# InkTime.net
KiCad netlist of a schematic drawn in EAGLE
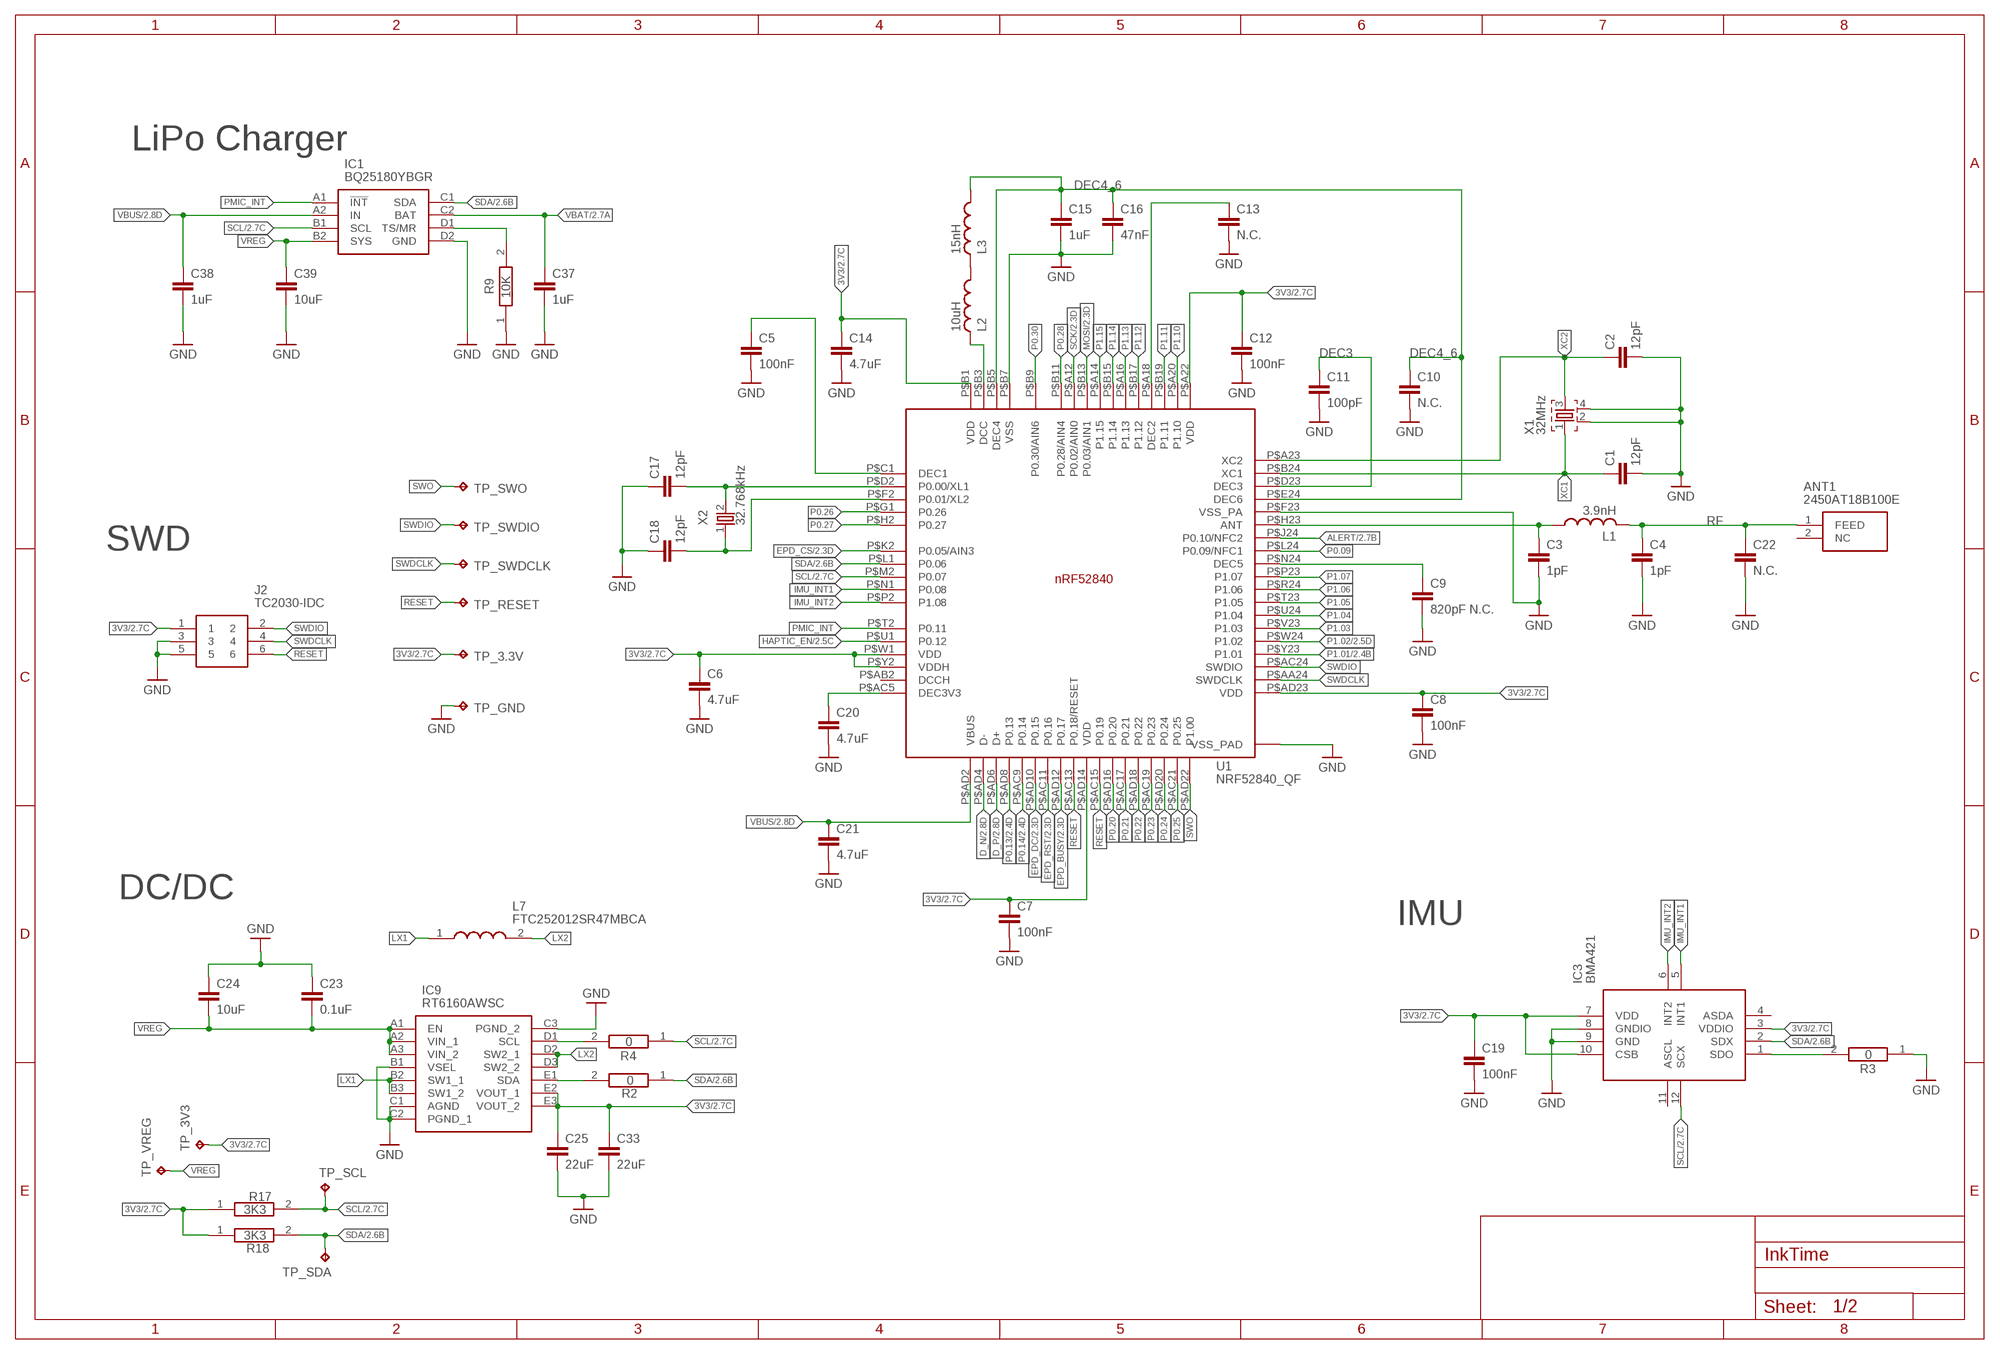
[diagram p0: schematic, sheet 1]
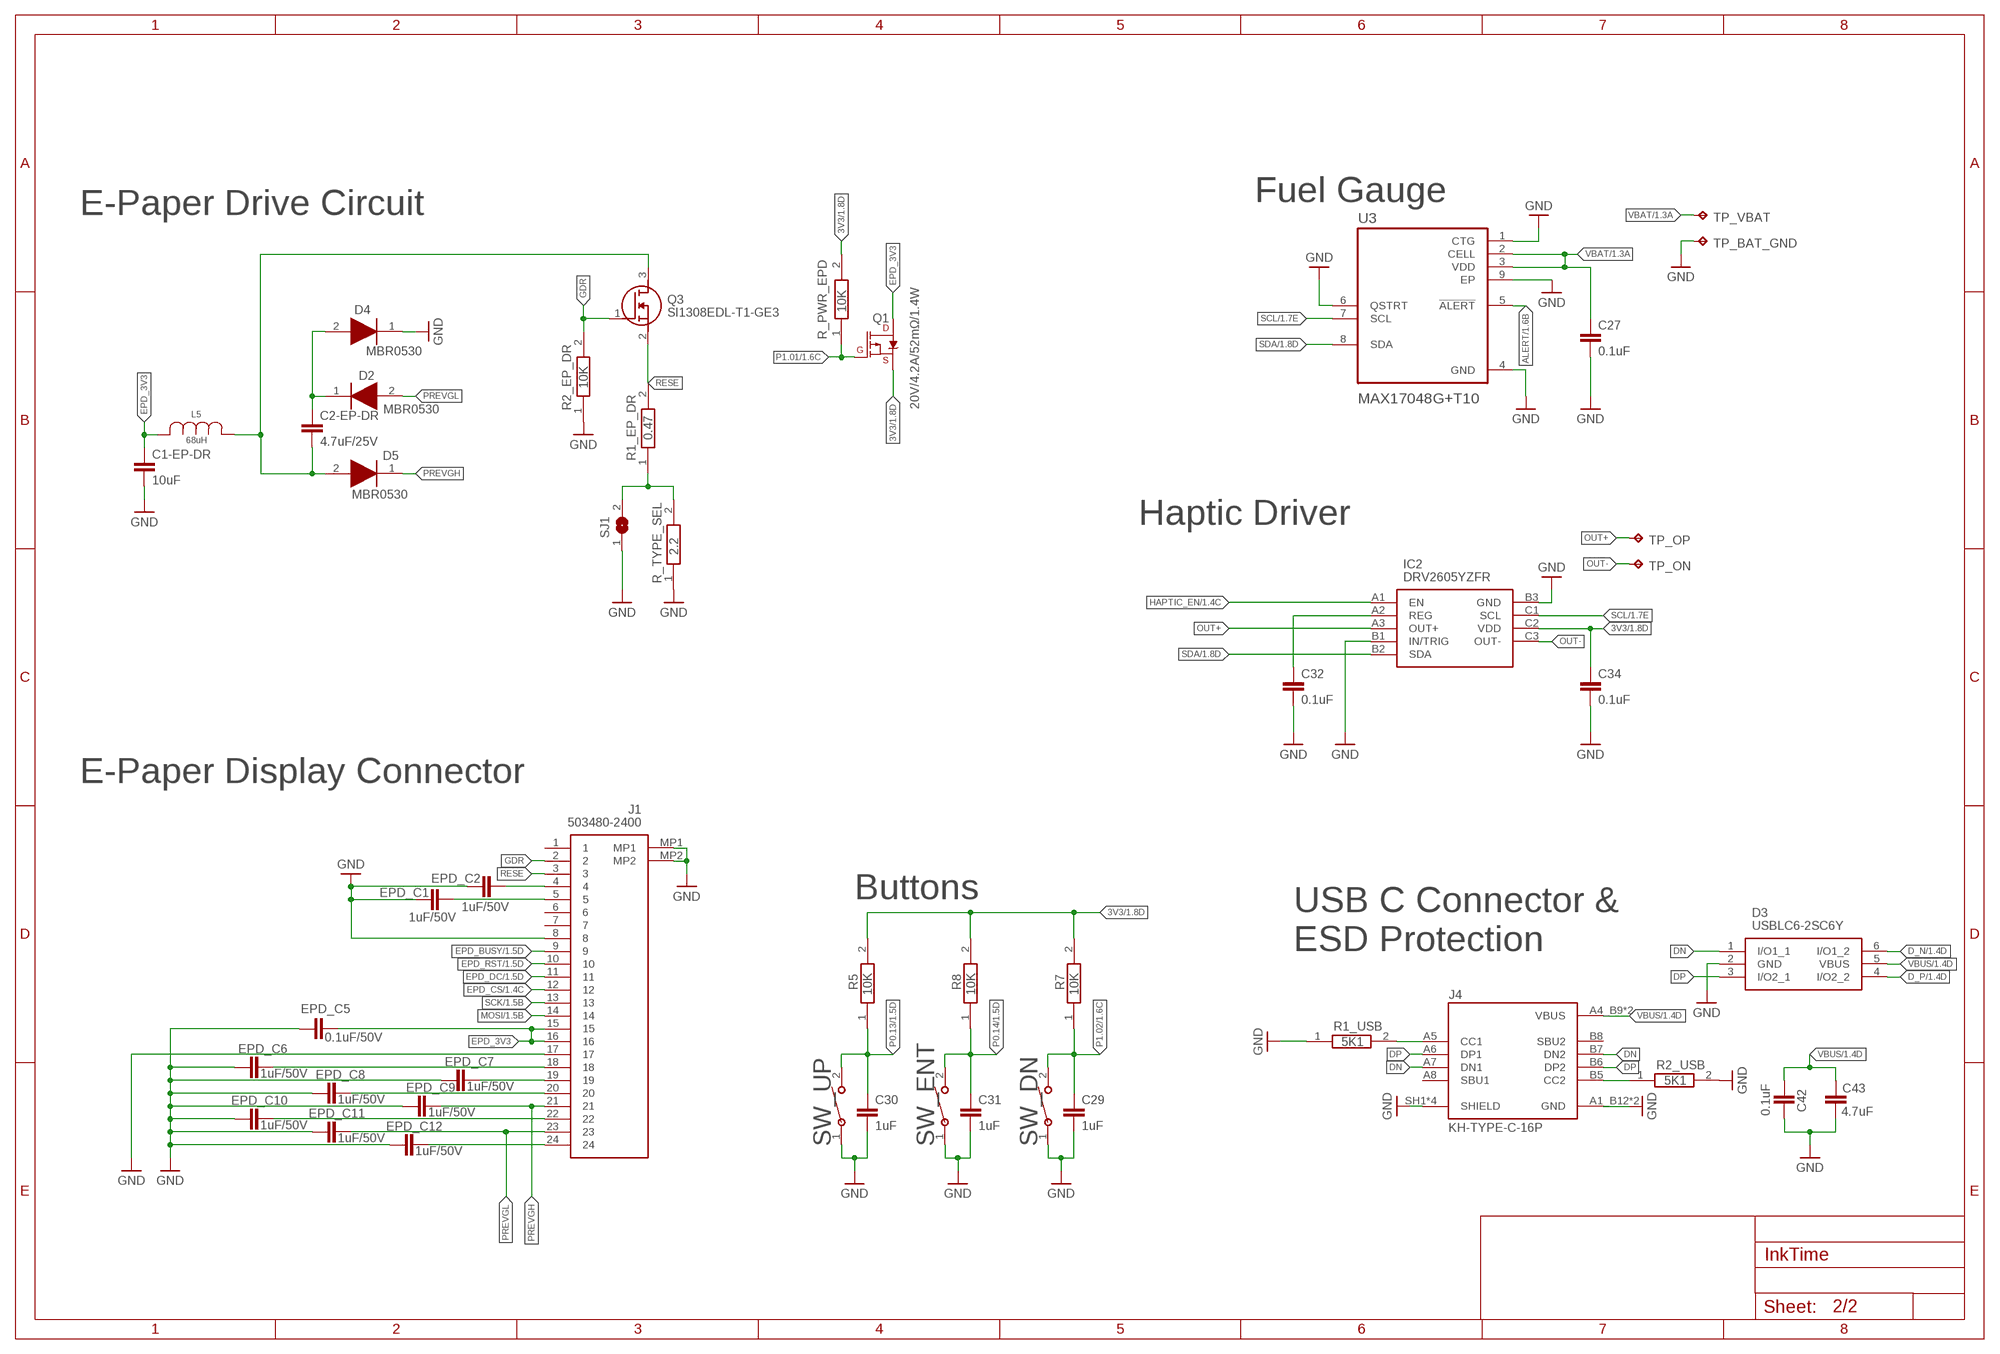
[diagram p1: schematic, sheet 2]

(export (version "E")
  (design (tool "Eeschema 10.0.6"))
  (components
    (comp (ref "C1-EP-DR")
      (value "10uF")
      (footprint "eagle-import:NORDIC_NRF_3_RESC0402_N")
      (libsource (lib "eagle-import") (part "NORDIC_NRF_3_CAPACITOR_0402_N"))
    )
    (comp (ref "C2-EP-DR")
      (value "4.7uF/25V")
      (footprint "eagle-import:NORDIC_NRF_3_RESC0402_N")
      (libsource (lib "eagle-import") (part "NORDIC_NRF_3_CAPACITOR_0402_N"))
    )
    (comp (ref "C27")
      (value "0.1uF")
      (footprint "eagle-import:NORDIC_NRF_3_RESC0201_N")
      (libsource (lib "eagle-import") (part "NORDIC_NRF_3_CAPACITOR_0201_N"))
    )
    (comp (ref "C29")
      (value "1uF")
      (footprint "eagle-import:NORDIC_NRF_3_RESC0402_N")
      (libsource (lib "eagle-import") (part "NORDIC_NRF_3_CAPACITOR_0402_N"))
    )
    (comp (ref "C30")
      (value "1uF")
      (footprint "eagle-import:NORDIC_NRF_3_RESC0402_N")
      (libsource (lib "eagle-import") (part "NORDIC_NRF_3_CAPACITOR_0402_N"))
    )
    (comp (ref "C31")
      (value "1uF")
      (footprint "eagle-import:NORDIC_NRF_3_RESC0402_N")
      (libsource (lib "eagle-import") (part "NORDIC_NRF_3_CAPACITOR_0402_N"))
    )
    (comp (ref "C32")
      (value "0.1uF")
      (footprint "eagle-import:NORDIC_NRF_3_RESC0201_N")
      (libsource (lib "eagle-import") (part "NORDIC_NRF_3_CAPACITOR_0201_N"))
    )
    (comp (ref "C34")
      (value "0.1uF")
      (footprint "eagle-import:NORDIC_NRF_3_RESC0201_N")
      (libsource (lib "eagle-import") (part "NORDIC_NRF_3_CAPACITOR_0201_N"))
    )
    (comp (ref "C42")
      (value "0.1uF")
      (footprint "eagle-import:NORDIC_NRF_3_RESC0201_N")
      (libsource (lib "eagle-import") (part "NORDIC_NRF_3_CAPACITOR_0201_N"))
    )
    (comp (ref "C43")
      (value "4.7uF")
      (footprint "eagle-import:NORDIC_NRF_3_RESC0402_N")
      (libsource (lib "eagle-import") (part "NORDIC_NRF_3_CAPACITOR_0402_N"))
    )
    (comp (ref "D2")
      (value "MBR0530")
      (footprint "eagle-import:ESP32_C6_LIBRARY_5_SOD3716X135N")
      (fields (field (name "MF") "ON Semiconductor"))
      (libsource (lib "eagle-import") (part "ESP32_C6_LIBRARY_5_MBR0530"))
    )
    (comp (ref "D3")
      (value "USBLC6-2SC6Y")
      (footprint "eagle-import:ESP32_C6_LIBRARY_3_SOT95P280X145-6N")
      (fields (field (name "MF") "STMicroelectronics"))
      (libsource (lib "eagle-import") (part "ESP32_C6_LIBRARY_3_USBLC6-2SC6Y"))
    )
    (comp (ref "D4")
      (value "MBR0530")
      (footprint "eagle-import:ESP32_C6_LIBRARY_5_SOD3716X135N")
      (fields (field (name "MF") "ON Semiconductor"))
      (libsource (lib "eagle-import") (part "ESP32_C6_LIBRARY_5_MBR0530"))
    )
    (comp (ref "D5")
      (value "MBR0530")
      (footprint "eagle-import:ESP32_C6_LIBRARY_5_SOD3716X135N")
      (fields (field (name "MF") "ON Semiconductor"))
      (libsource (lib "eagle-import") (part "ESP32_C6_LIBRARY_5_MBR0530"))
    )
    (comp (ref "EPD_C1")
      (value "1uF/50V")
      (footprint "eagle-import:NORDIC_NRF_3_RESC0402_N")
      (libsource (lib "eagle-import") (part "NORDIC_NRF_3_CAPACITOR_0402_N"))
    )
    (comp (ref "EPD_C2")
      (value "1uF/50V")
      (footprint "eagle-import:NORDIC_NRF_3_RESC0402_N")
      (libsource (lib "eagle-import") (part "NORDIC_NRF_3_CAPACITOR_0402_N"))
    )
    (comp (ref "EPD_C5")
      (value "0.1uF/50V")
      (footprint "eagle-import:NORDIC_NRF_3_RESC0402_N")
      (libsource (lib "eagle-import") (part "NORDIC_NRF_3_CAPACITOR_0402_N"))
    )
    (comp (ref "EPD_C6")
      (value "1uF/50V")
      (footprint "eagle-import:NORDIC_NRF_3_RESC0402_N")
      (libsource (lib "eagle-import") (part "NORDIC_NRF_3_CAPACITOR_0402_N"))
    )
    (comp (ref "EPD_C7")
      (value "1uF/50V")
      (footprint "eagle-import:NORDIC_NRF_3_RESC0402_N")
      (libsource (lib "eagle-import") (part "NORDIC_NRF_3_CAPACITOR_0402_N"))
    )
    (comp (ref "EPD_C8")
      (value "1uF/50V")
      (footprint "eagle-import:NORDIC_NRF_3_RESC0402_N")
      (libsource (lib "eagle-import") (part "NORDIC_NRF_3_CAPACITOR_0402_N"))
    )
    (comp (ref "EPD_C9")
      (value "1uF/50V")
      (footprint "eagle-import:NORDIC_NRF_3_RESC0402_N")
      (libsource (lib "eagle-import") (part "NORDIC_NRF_3_CAPACITOR_0402_N"))
    )
    (comp (ref "EPD_C10")
      (value "1uF/50V")
      (footprint "eagle-import:NORDIC_NRF_3_RESC0402_N")
      (libsource (lib "eagle-import") (part "NORDIC_NRF_3_CAPACITOR_0402_N"))
    )
    (comp (ref "EPD_C11")
      (value "1uF/50V")
      (footprint "eagle-import:NORDIC_NRF_3_RESC0402_N")
      (libsource (lib "eagle-import") (part "NORDIC_NRF_3_CAPACITOR_0402_N"))
    )
    (comp (ref "EPD_C12")
      (value "1uF/50V")
      (footprint "eagle-import:NORDIC_NRF_3_RESC0402_N")
      (libsource (lib "eagle-import") (part "NORDIC_NRF_3_CAPACITOR_0402_N"))
    )
    (comp (ref "IC2")
      (value "DRV2605YZFR")
      (footprint "eagle-import:DRV2605YZFR_BGA9C50P3X3_144X144X62")
      (libsource (lib "eagle-import") (part "DRV2605YZFR_DRV2605YZFR"))
    )
    (comp (ref "J1")
      (value "503480-2400")
      (footprint "eagle-import:503480-2400_5034802400")
      (fields (field (name "MOUSER_PART_NUMBER") "538-503480-2400"))
      (libsource (lib "eagle-import") (part "503480-2400_503480-24003D"))
    )
    (comp (ref "J4")
      (value "KH-TYPE-C-16P")
      (footprint "eagle-import:KH-TYPE-C-16P_KINGHELM_KH-TYPE-C-16P")
      (fields (field (name "MF") "kinghelm"))
      (libsource (lib "eagle-import") (part "KH-TYPE-C-16P_KH-TYPE-C-16P"))
    )
    (comp (ref "L5")
      (value "68uH")
      (footprint "eagle-import:ESP32_C6_LIBRARY_2_IND_4828-WE-TPC_WRE")
      (fields
        (field (name "MANUFACTURER_PART_NUMBER") "744043680")
        (field (name "COPYRIGHT") "Copyright (C) 2024 Ultra Librarian. All rights reserved.")
      )
      (libsource (lib "eagle-import") (part "ESP32_C6_LIBRARY_2_744043680IND_4828-WE-TPC_WRE"))
    )
    (comp (ref "Q1")
      (value "20V/4.2A/52mΩ/1.4W")
      (footprint "eagle-import:ESP32_C6_LIBRARY_4_ESP32_C6_LIBRARY_4_ESP32_C6_LIBRARY_4_ESP32_C6_LIBRARY_4_ESP32_WROVER_SPARKFUN-DISCRETESEMI_SOT23-3")
      (libsource (lib "eagle-import") (part "ESP32_C6_LIBRARY_4_ESP32_WROVER_SPARKFUN-DISCRETESEMI_MOSFET_PCH-DMG2305UX-7"))
    )
    (comp (ref "Q3")
      (value "SI1308EDL-T1-GE3")
      (footprint "eagle-import:ESP32_C6_LIBRARY_6_SOT65P210X110-3N")
      (fields (field (name "MF") "Vishay Siliconix"))
      (libsource (lib "eagle-import") (part "ESP32_C6_LIBRARY_6_SI1308EDL-T1-GE3"))
    )
    (comp (ref "R1_EP_DR")
      (value "0.47")
      (footprint "eagle-import:CPF0201D7K68C1_0201")
      (libsource (lib "eagle-import") (part "CPF0201D7K68C1_CPF0201D7K68C1"))
    )
    (comp (ref "R1_USB")
      (value "5K1")
      (footprint "eagle-import:CPF0201D7K68C1_0201")
      (libsource (lib "eagle-import") (part "CPF0201D7K68C1_CPF0201D7K68C1"))
    )
    (comp (ref "R2_EP_DR")
      (value "10K")
      (footprint "eagle-import:CPF0201D7K68C1_0201")
      (libsource (lib "eagle-import") (part "CPF0201D7K68C1_CPF0201D7K68C1"))
    )
    (comp (ref "R2_USB")
      (value "5K1")
      (footprint "eagle-import:CPF0201D7K68C1_0201")
      (libsource (lib "eagle-import") (part "CPF0201D7K68C1_CPF0201D7K68C1"))
    )
    (comp (ref "R5")
      (value "10K")
      (footprint "eagle-import:CPF0201D7K68C1_0201")
      (libsource (lib "eagle-import") (part "CPF0201D7K68C1_CPF0201D7K68C1"))
    )
    (comp (ref "R7")
      (value "10K")
      (footprint "eagle-import:CPF0201D7K68C1_0201")
      (libsource (lib "eagle-import") (part "CPF0201D7K68C1_CPF0201D7K68C1"))
    )
    (comp (ref "R8")
      (value "10K")
      (footprint "eagle-import:CPF0201D7K68C1_0201")
      (libsource (lib "eagle-import") (part "CPF0201D7K68C1_CPF0201D7K68C1"))
    )
    (comp (ref "R_PWR_EPD")
      (value "10K")
      (footprint "eagle-import:CPF0201D7K68C1_0201")
      (libsource (lib "eagle-import") (part "CPF0201D7K68C1_CPF0201D7K68C1"))
    )
    (comp (ref "R_TYPE_SEL")
      (value "2.2")
      (footprint "eagle-import:CPF0201D7K68C1_0201")
      (libsource (lib "eagle-import") (part "CPF0201D7K68C1_CPF0201D7K68C1"))
    )
    (comp (ref "SJ1")
      (value "ESP32_C6_LIBRARY_7_JUMPER_SJ")
      (footprint "eagle-import:ESP32_C6_LIBRARY_7_JUMPER_SJ")
      (libsource (lib "eagle-import") (part "ESP32_C6_LIBRARY_7_JUMPER_SJ"))
    )
    (comp (ref "SW_DN")
      (value "2025-10-22_07-23-44_LIBRARY_EVP-AKE31ASW_EVP-AKE31A_PAN")
      (footprint "eagle-import:2025-10-22_07-23-44_LIBRARY_SW_EVP-AKE31A_PAN")
      (fields
        (field (name "MANUFACTURER_PART_NUMBER") "EVP-AKE31A")
        (field (name "COPYRIGHT") "Copyright (C) 2025 Ultra Librarian. All rights reserved.")
      )
      (libsource (lib "eagle-import") (part "2025-10-22_07-23-44_LIBRARY_EVP-AKE31ASW_EVP-AKE31A_PAN"))
    )
    (comp (ref "SW_ENT")
      (value "2025-10-22_07-23-44_LIBRARY_EVP-AKE31ASW_EVP-AKE31A_PAN")
      (footprint "eagle-import:2025-10-22_07-23-44_LIBRARY_SW_EVP-AKE31A_PAN")
      (fields
        (field (name "MANUFACTURER_PART_NUMBER") "EVP-AKE31A")
        (field (name "COPYRIGHT") "Copyright (C) 2025 Ultra Librarian. All rights reserved.")
      )
      (libsource (lib "eagle-import") (part "2025-10-22_07-23-44_LIBRARY_EVP-AKE31ASW_EVP-AKE31A_PAN"))
    )
    (comp (ref "SW_UP")
      (value "2025-10-22_07-23-44_LIBRARY_EVP-AKE31ASW_EVP-AKE31A_PAN")
      (footprint "eagle-import:2025-10-22_07-23-44_LIBRARY_SW_EVP-AKE31A_PAN")
      (fields
        (field (name "MANUFACTURER_PART_NUMBER") "EVP-AKE31A")
        (field (name "COPYRIGHT") "Copyright (C) 2025 Ultra Librarian. All rights reserved.")
      )
      (libsource (lib "eagle-import") (part "2025-10-22_07-23-44_LIBRARY_EVP-AKE31ASW_EVP-AKE31A_PAN"))
    )
    (comp (ref "TP_BAT_GND")
      (value "HECTOR_WATCH_1_TPTP20R")
      (footprint "eagle-import:HECTOR_WATCH_1_TP20R")
      (libsource (lib "eagle-import") (part "HECTOR_WATCH_1_TPTP20R"))
    )
    (comp (ref "TP_ON")
      (value "HECTOR_WATCH_1_TPTP20R")
      (footprint "eagle-import:HECTOR_WATCH_1_TP20R")
      (libsource (lib "eagle-import") (part "HECTOR_WATCH_1_TPTP20R"))
    )
    (comp (ref "TP_OP")
      (value "HECTOR_WATCH_1_TPTP20R")
      (footprint "eagle-import:HECTOR_WATCH_1_TP20R")
      (libsource (lib "eagle-import") (part "HECTOR_WATCH_1_TPTP20R"))
    )
    (comp (ref "TP_VBAT")
      (value "HECTOR_WATCH_1_TPTP20R")
      (footprint "eagle-import:HECTOR_WATCH_1_TP20R")
      (libsource (lib "eagle-import") (part "HECTOR_WATCH_1_TPTP20R"))
    )
    (comp (ref "U3")
      (value "MAX17048G+T10")
      (footprint "eagle-import:ESP32_C6_LIBRARY_SON50P200X200X80-9N")
      (fields (field (name "MF") "Analog Devices"))
      (libsource (lib "eagle-import") (part "ESP32_C6_LIBRARY_MAX17048G+T10"))
    )
    (comp (ref "ANT1")
      (value "2450AT18B100E")
      (footprint "eagle-import:2450AT18B100E_ANTC3216X140N")
      (fields (field (name "MOUSER_PART_NUMBER") "609-2450AT18B100E"))
      (libsource (lib "eagle-import") (part "2450AT18B100E_2450AT18B100E3D"))
    )
    (comp (ref "C1")
      (value "12pF")
      (footprint "eagle-import:NORDIC_NRF_3_RESC0201_N")
      (libsource (lib "eagle-import") (part "NORDIC_NRF_3_CAPACITOR_0201_N"))
    )
    (comp (ref "C2")
      (value "12pF")
      (footprint "eagle-import:NORDIC_NRF_3_RESC0201_N")
      (libsource (lib "eagle-import") (part "NORDIC_NRF_3_CAPACITOR_0201_N"))
    )
    (comp (ref "C3")
      (value "1pF")
      (footprint "eagle-import:NORDIC_NRF_3_RESC0201_N")
      (libsource (lib "eagle-import") (part "NORDIC_NRF_3_CAPACITOR_0201_N"))
    )
    (comp (ref "C4")
      (value "1pF")
      (footprint "eagle-import:NORDIC_NRF_3_RESC0201_N")
      (libsource (lib "eagle-import") (part "NORDIC_NRF_3_CAPACITOR_0201_N"))
    )
    (comp (ref "C5")
      (value "100nF")
      (footprint "eagle-import:NORDIC_NRF_3_RESC0201_N")
      (libsource (lib "eagle-import") (part "NORDIC_NRF_3_CAPACITOR_0201_N"))
    )
    (comp (ref "C6")
      (value "4.7uF")
      (footprint "eagle-import:NORDIC_NRF_3_RESC0402_N")
      (libsource (lib "eagle-import") (part "NORDIC_NRF_3_CAPACITOR_0402_N"))
    )
    (comp (ref "C7")
      (value "100nF")
      (footprint "eagle-import:NORDIC_NRF_3_RESC0201_N")
      (libsource (lib "eagle-import") (part "NORDIC_NRF_3_CAPACITOR_0201_N"))
    )
    (comp (ref "C8")
      (value "100nF")
      (footprint "eagle-import:NORDIC_NRF_3_RESC0201_N")
      (libsource (lib "eagle-import") (part "NORDIC_NRF_3_CAPACITOR_0201_N"))
    )
    (comp (ref "C9")
      (value "820pF N.C.")
      (footprint "eagle-import:NORDIC_NRF_3_RESC0201_N")
      (libsource (lib "eagle-import") (part "NORDIC_NRF_3_CAPACITOR_0201_N"))
    )
    (comp (ref "C10")
      (value "N.C.")
      (footprint "eagle-import:NORDIC_NRF_3_RESC0201_N")
      (libsource (lib "eagle-import") (part "NORDIC_NRF_3_CAPACITOR_0201_N"))
    )
    (comp (ref "C11")
      (value "100pF")
      (footprint "eagle-import:NORDIC_NRF_3_RESC0201_N")
      (libsource (lib "eagle-import") (part "NORDIC_NRF_3_CAPACITOR_0201_N"))
    )
    (comp (ref "C12")
      (value "100nF")
      (footprint "eagle-import:NORDIC_NRF_3_RESC0201_N")
      (libsource (lib "eagle-import") (part "NORDIC_NRF_3_CAPACITOR_0201_N"))
    )
    (comp (ref "C13")
      (value "N.C.")
      (footprint "eagle-import:NORDIC_NRF_3_RESC0201_N")
      (libsource (lib "eagle-import") (part "NORDIC_NRF_3_CAPACITOR_0201_N"))
    )
    (comp (ref "C14")
      (value "4.7uF")
      (footprint "eagle-import:NORDIC_NRF_3_RESC0402_N")
      (libsource (lib "eagle-import") (part "NORDIC_NRF_3_CAPACITOR_0402_N"))
    )
    (comp (ref "C15")
      (value "1uF")
      (footprint "eagle-import:NORDIC_NRF_3_RESC0402_N")
      (libsource (lib "eagle-import") (part "NORDIC_NRF_3_CAPACITOR_0402_N"))
    )
    (comp (ref "C16")
      (value "47nF")
      (footprint "eagle-import:NORDIC_NRF_3_RESC0201_N")
      (libsource (lib "eagle-import") (part "NORDIC_NRF_3_CAPACITOR_0201_N"))
    )
    (comp (ref "C17")
      (value "12pF")
      (footprint "eagle-import:NORDIC_NRF_3_RESC0201_N")
      (libsource (lib "eagle-import") (part "NORDIC_NRF_3_CAPACITOR_0201_N"))
    )
    (comp (ref "C18")
      (value "12pF")
      (footprint "eagle-import:NORDIC_NRF_3_RESC0201_N")
      (libsource (lib "eagle-import") (part "NORDIC_NRF_3_CAPACITOR_0201_N"))
    )
    (comp (ref "C19")
      (value "100nF")
      (footprint "eagle-import:NORDIC_NRF_3_RESC0201_N")
      (libsource (lib "eagle-import") (part "NORDIC_NRF_3_CAPACITOR_0201_N"))
    )
    (comp (ref "C20")
      (value "4.7uF")
      (footprint "eagle-import:NORDIC_NRF_3_RESC0402_N")
      (libsource (lib "eagle-import") (part "NORDIC_NRF_3_CAPACITOR_0402_N"))
    )
    (comp (ref "C21")
      (value "4.7uF")
      (footprint "eagle-import:NORDIC_NRF_3_RESC0402_N")
      (libsource (lib "eagle-import") (part "NORDIC_NRF_3_CAPACITOR_0402_N"))
    )
    (comp (ref "C22")
      (value "N.C.")
      (footprint "eagle-import:NORDIC_NRF_3_RESC0201_N")
      (libsource (lib "eagle-import") (part "NORDIC_NRF_3_CAPACITOR_0201_N"))
    )
    (comp (ref "C23")
      (value "0.1uF")
      (footprint "eagle-import:NORDIC_NRF_3_RESC0201_N")
      (libsource (lib "eagle-import") (part "NORDIC_NRF_3_CAPACITOR_0201_N"))
    )
    (comp (ref "C24")
      (value "10uF")
      (footprint "eagle-import:NORDIC_NRF_3_RESC0402_N")
      (libsource (lib "eagle-import") (part "NORDIC_NRF_3_CAPACITOR_0402_N"))
    )
    (comp (ref "C25")
      (value "22uF")
      (footprint "eagle-import:NORDIC_NRF_3_RESC0402_N")
      (libsource (lib "eagle-import") (part "NORDIC_NRF_3_CAPACITOR_0402_N"))
    )
    (comp (ref "C33")
      (value "22uF")
      (footprint "eagle-import:NORDIC_NRF_3_RESC0402_N")
      (libsource (lib "eagle-import") (part "NORDIC_NRF_3_CAPACITOR_0402_N"))
    )
    (comp (ref "C37")
      (value "1uF")
      (footprint "eagle-import:NORDIC_NRF_3_RESC0402_N")
      (libsource (lib "eagle-import") (part "NORDIC_NRF_3_CAPACITOR_0402_N"))
    )
    (comp (ref "C38")
      (value "1uF")
      (footprint "eagle-import:NORDIC_NRF_3_RESC0402_N")
      (libsource (lib "eagle-import") (part "NORDIC_NRF_3_CAPACITOR_0402_N"))
    )
    (comp (ref "C39")
      (value "10uF")
      (footprint "eagle-import:NORDIC_NRF_3_RESC0402_N")
      (libsource (lib "eagle-import") (part "NORDIC_NRF_3_CAPACITOR_0402_N"))
    )
    (comp (ref "IC1")
      (value "BQ25180YBGR")
      (footprint "eagle-import:BQ25180YBGR_BGA8C40P2X4_100X155X50")
      (fields (field (name "MOUSER_PART_NUMBER") "595-BQ25180YBGR"))
      (libsource (lib "eagle-import") (part "BQ25180YBGR_BQ25180YBGR"))
    )
    (comp (ref "IC3")
      (value "BMA421")
      (footprint "eagle-import:BMA423_BMA423")
      (fields (field (name "ARROW_PART_NUMBER") "BMA423") (field (name "MOUSER_PART_NUMBER") "262-BMA423"))
      (libsource (lib "eagle-import") (part "BMA421_BMA421"))
    )
    (comp (ref "IC9")
      (value "RT6160AWSC")
      (footprint "eagle-import:RT6160AWSC_BGA15C40P3X5_140X230X60")
      (fields (field (name "MOUSER_PART_NUMBER") "835-RT6160AWSC"))
      (libsource (lib "eagle-import") (part "RT6160AWSC_RT6160AWSC"))
    )
    (comp (ref "J2")
      (value "TC2030-IDC")
      (footprint "eagle-import:TC2030-IDC_TC2030IDC")
      (libsource (lib "eagle-import") (part "TC2030-IDC_TC2030-IDC"))
    )
    (comp (ref "L1")
      (value "3.9nH")
      (footprint "eagle-import:NORDIC_NRF_2_RESC0402_N")
      (libsource (lib "eagle-import") (part "NORDIC_NRF_2_INDUCTOR_0402_N"))
    )
    (comp (ref "L2")
      (value "10uH")
      (footprint "eagle-import:NORDIC_NRF_2_RESC0603_N")
      (libsource (lib "eagle-import") (part "NORDIC_NRF_2_INDUCTOR_0603_N"))
    )
    (comp (ref "L3")
      (value "15nH")
      (footprint "eagle-import:NORDIC_NRF_2_RESC0402_N")
      (libsource (lib "eagle-import") (part "NORDIC_NRF_2_INDUCTOR_0402_N"))
    )
    (comp (ref "L7")
      (value "FTC252012SR47MBCA")
      (footprint "eagle-import:MLP2016SR47MT0S1_INDC2016X100N")
      (libsource (lib "eagle-import") (part "MLP2016SR47MT0S1_FTC252012SR47MBCA"))
    )
    (comp (ref "R2")
      (value "0")
      (footprint "eagle-import:CPF0201D7K68C1_0201")
      (libsource (lib "eagle-import") (part "CPF0201D7K68C1_CPF0201D7K68C1"))
    )
    (comp (ref "R3")
      (value "0")
      (footprint "eagle-import:CPF0201D7K68C1_0201")
      (libsource (lib "eagle-import") (part "CPF0201D7K68C1_CPF0201D7K68C1"))
    )
    (comp (ref "R4")
      (value "0")
      (footprint "eagle-import:CPF0201D7K68C1_0201")
      (libsource (lib "eagle-import") (part "CPF0201D7K68C1_CPF0201D7K68C1"))
    )
    (comp (ref "R9")
      (value "10K")
      (footprint "eagle-import:CPF0201D7K68C1_0201")
      (libsource (lib "eagle-import") (part "CPF0201D7K68C1_CPF0201D7K68C1"))
    )
    (comp (ref "R17")
      (value "3K3")
      (footprint "eagle-import:CPF0201D7K68C1_0201")
      (libsource (lib "eagle-import") (part "CPF0201D7K68C1_CPF0201D7K68C1"))
    )
    (comp (ref "R18")
      (value "3K3")
      (footprint "eagle-import:CPF0201D7K68C1_0201")
      (libsource (lib "eagle-import") (part "CPF0201D7K68C1_CPF0201D7K68C1"))
    )
    (comp (ref "TP_3.3V")
      (value "HECTOR_WATCH_1_TPTP20R")
      (footprint "eagle-import:HECTOR_WATCH_1_TP20R")
      (libsource (lib "eagle-import") (part "HECTOR_WATCH_1_TPTP20R"))
    )
    (comp (ref "TP_3V3")
      (value "HECTOR_WATCH_1_TPTP20R")
      (footprint "eagle-import:HECTOR_WATCH_1_TP20R")
      (libsource (lib "eagle-import") (part "HECTOR_WATCH_1_TPTP20R"))
    )
    (comp (ref "TP_GND")
      (value "HECTOR_WATCH_1_TPTP20R")
      (footprint "eagle-import:HECTOR_WATCH_1_TP20R")
      (libsource (lib "eagle-import") (part "HECTOR_WATCH_1_TPTP20R"))
    )
    (comp (ref "TP_RESET")
      (value "HECTOR_WATCH_1_TPTP20R")
      (footprint "eagle-import:HECTOR_WATCH_1_TP20R")
      (libsource (lib "eagle-import") (part "HECTOR_WATCH_1_TPTP20R"))
    )
    (comp (ref "TP_SCL")
      (value "HECTOR_WATCH_1_TPTP20R")
      (footprint "eagle-import:HECTOR_WATCH_1_TP20R")
      (libsource (lib "eagle-import") (part "HECTOR_WATCH_1_TPTP20R"))
    )
    (comp (ref "TP_SDA")
      (value "HECTOR_WATCH_1_TPTP20R")
      (footprint "eagle-import:HECTOR_WATCH_1_TP20R")
      (libsource (lib "eagle-import") (part "HECTOR_WATCH_1_TPTP20R"))
    )
    (comp (ref "TP_SWDCLK")
      (value "HECTOR_WATCH_1_TPTP20R")
      (footprint "eagle-import:HECTOR_WATCH_1_TP20R")
      (libsource (lib "eagle-import") (part "HECTOR_WATCH_1_TPTP20R"))
    )
    (comp (ref "TP_SWDIO")
      (value "HECTOR_WATCH_1_TPTP20R")
      (footprint "eagle-import:HECTOR_WATCH_1_TP20R")
      (libsource (lib "eagle-import") (part "HECTOR_WATCH_1_TPTP20R"))
    )
    (comp (ref "TP_SWO")
      (value "HECTOR_WATCH_1_TPTP20R")
      (footprint "eagle-import:HECTOR_WATCH_1_TP20R")
      (libsource (lib "eagle-import") (part "HECTOR_WATCH_1_TPTP20R"))
    )
    (comp (ref "TP_VREG")
      (value "HECTOR_WATCH_1_TPTP20R")
      (footprint "eagle-import:HECTOR_WATCH_1_TP20R")
      (libsource (lib "eagle-import") (part "HECTOR_WATCH_1_TPTP20R"))
    )
    (comp (ref "U1")
      (value "NRF52840_QF")
      (footprint "eagle-import:NORDIC_NRF_4_AQFN50P700X700X85_HS-74N_PINCLEAN")
      (libsource (lib "eagle-import") (part "NORDIC_NRF_4_NRF52840_QF_PINCLEAN"))
    )
    (comp (ref "X1")
      (value "32MHz")
      (footprint "eagle-import:NORDIC_NRF_BT-XTAL_2016_N")
      (libsource (lib "eagle-import") (part "NORDIC_NRF_XTAL_32MHZ"))
    )
    (comp (ref "X2")
      (value "32.768kHz")
      (footprint "eagle-import:NORDIC_NRF_1_XTAL_3215_N")
      (libsource (lib "eagle-import") (part "NORDIC_NRF_1_XTAL_32KHZ"))
    )
  )
  (nets
    (net (code "1") (name "3V3") (class "Default")
      (node (ref "C12") (pin "1") (pinfunction "1_1") (pintype "passive"))
      (node (ref "C14") (pin "1") (pinfunction "1_1") (pintype "passive"))
      (node (ref "C19") (pin "1") (pinfunction "1_1") (pintype "passive"))
      (node (ref "C25") (pin "1") (pinfunction "1_1") (pintype "passive"))
      (node (ref "C33") (pin "1") (pinfunction "1_1") (pintype "passive"))
      (node (ref "C34") (pin "1") (pinfunction "1_1") (pintype "passive"))
      (node (ref "C6") (pin "1") (pinfunction "1_1") (pintype "passive"))
      (node (ref "C7") (pin "1") (pinfunction "1_1") (pintype "passive"))
      (node (ref "C8") (pin "1") (pinfunction "1_1") (pintype "passive"))
      (node (ref "IC2") (pin "C2") (pinfunction "VDD_C2") (pintype "bidirectional"))
      (node (ref "IC3") (pin "10") (pinfunction "CSB_10") (pintype "bidirectional"))
      (node (ref "IC3") (pin "3") (pinfunction "VDDIO_3") (pintype "bidirectional"))
      (node (ref "IC3") (pin "7") (pinfunction "VDD_7") (pintype "bidirectional"))
      (node (ref "IC9") (pin "E2") (pinfunction "VOUT_1_E2") (pintype "bidirectional"))
      (node (ref "IC9") (pin "E3") (pinfunction "VOUT_2_E3") (pintype "bidirectional"))
      (node (ref "J2") (pin "1") (pinfunction "1_1") (pintype "bidirectional"))
      (node (ref "Q1") (pin "2") (pinfunction "S_2") (pintype "bidirectional"))
      (node (ref "R17") (pin "1") (pinfunction "1_1") (pintype "bidirectional"))
      (node (ref "R18") (pin "1") (pinfunction "1_1") (pintype "bidirectional"))
      (node (ref "R5") (pin "2") (pinfunction "2_2") (pintype "bidirectional"))
      (node (ref "R7") (pin "2") (pinfunction "2_2") (pintype "bidirectional"))
      (node (ref "R8") (pin "2") (pinfunction "2_2") (pintype "bidirectional"))
      (node (ref "R_PWR_EPD") (pin "2") (pinfunction "2_2") (pintype "bidirectional"))
      (node (ref "TP_3.3V") (pin "TP") (pinfunction "TP_TP") (pintype "input"))
      (node (ref "TP_3V3") (pin "TP") (pinfunction "TP_TP") (pintype "input"))
      (node (ref "U1") (pin "P$A22") (pinfunction "VDD_P$A22") (pintype "power_in"))
      (node (ref "U1") (pin "P$AD14") (pinfunction "VDD_P$AD14") (pintype "power_in"))
      (node (ref "U1") (pin "P$AD23") (pinfunction "VDD_P$AD23") (pintype "power_in"))
      (node (ref "U1") (pin "P$B1") (pinfunction "VDD_P$B1") (pintype "power_in"))
      (node (ref "U1") (pin "P$W1") (pinfunction "VDD_P$W1") (pintype "power_in"))
      (node (ref "U1") (pin "P$Y2") (pinfunction "VDDH_P$Y2") (pintype "power_in"))
    )
    (net (code "2") (name "ALERT") (class "Default")
      (node (ref "U1") (pin "P$J24") (pinfunction "P0.10/NFC2_P$J24") (pintype "bidirectional"))
      (node (ref "U3") (pin "5") (pinfunction "~{ALERT}_5") (pintype "output"))
    )
    (net (code "3") (name "DEC3") (class "Default")
      (node (ref "C11") (pin "1") (pinfunction "1_1") (pintype "passive"))
      (node (ref "U1") (pin "P$D23") (pinfunction "DEC3_P$D23") (pintype "bidirectional"))
    )
    (net (code "4") (name "DEC4_6") (class "Default")
      (node (ref "C10") (pin "1") (pinfunction "1_1") (pintype "passive"))
      (node (ref "C15") (pin "1") (pinfunction "1_1") (pintype "passive"))
      (node (ref "C16") (pin "1") (pinfunction "1_1") (pintype "passive"))
      (node (ref "L3") (pin "1") (pinfunction "1_1") (pintype "passive"))
      (node (ref "U1") (pin "P$B5") (pinfunction "DEC4_P$B5") (pintype "power_in"))
      (node (ref "U1") (pin "P$E24") (pinfunction "DEC6_P$E24") (pintype "bidirectional"))
    )
    (net (code "5") (name "DN") (class "Default")
      (node (ref "D3") (pin "1") (pinfunction "I/O1_1_1") (pintype "bidirectional"))
      (node (ref "J4") (pin "A7") (pinfunction "DN1_A7") (pintype "bidirectional"))
      (node (ref "J4") (pin "B7") (pinfunction "DN2_B7") (pintype "bidirectional"))
    )
    (net (code "6") (name "DP") (class "Default")
      (node (ref "D3") (pin "3") (pinfunction "I/O2_1_3") (pintype "bidirectional"))
      (node (ref "J4") (pin "A6") (pinfunction "DP1_A6") (pintype "bidirectional"))
      (node (ref "J4") (pin "B6") (pinfunction "DP2_B6") (pintype "bidirectional"))
    )
    (net (code "7") (name "D_N") (class "Default")
      (node (ref "D3") (pin "6") (pinfunction "I/O1_2_6") (pintype "bidirectional"))
      (node (ref "U1") (pin "P$AD4") (pinfunction "D-_P$AD4") (pintype "bidirectional"))
    )
    (net (code "8") (name "D_P") (class "Default")
      (node (ref "D3") (pin "4") (pinfunction "I/O2_2_4") (pintype "bidirectional"))
      (node (ref "U1") (pin "P$AD6") (pinfunction "D+_P$AD6") (pintype "bidirectional"))
    )
    (net (code "9") (name "EPD_3V3") (class "Default")
      (node (ref "C1-EP-DR") (pin "1") (pinfunction "1_1") (pintype "passive"))
      (node (ref "EPD_C5") (pin "2") (pinfunction "2_2") (pintype "passive"))
      (node (ref "J1") (pin "15") (pinfunction "15_15") (pintype "bidirectional"))
      (node (ref "J1") (pin "16") (pinfunction "16_16") (pintype "bidirectional"))
      (node (ref "L5") (pin "2") (pinfunction "2_2") (pintype "passive"))
      (node (ref "Q1") (pin "3") (pinfunction "D_3") (pintype "bidirectional"))
    )
    (net (code "10") (name "EPD_BUSY") (class "Default")
      (node (ref "J1") (pin "9") (pinfunction "9_9") (pintype "bidirectional"))
      (node (ref "U1") (pin "P$AD12") (pinfunction "P0.17_P$AD12") (pintype "bidirectional"))
    )
    (net (code "11") (name "EPD_CS") (class "Default")
      (node (ref "J1") (pin "12") (pinfunction "12_12") (pintype "bidirectional"))
      (node (ref "U1") (pin "P$K2") (pinfunction "P0.05/AIN3_P$K2") (pintype "bidirectional"))
    )
    (net (code "12") (name "EPD_DC") (class "Default")
      (node (ref "J1") (pin "11") (pinfunction "11_11") (pintype "bidirectional"))
      (node (ref "U1") (pin "P$AD10") (pinfunction "P0.15_P$AD10") (pintype "bidirectional"))
    )
    (net (code "13") (name "EPD_RST") (class "Default")
      (node (ref "J1") (pin "10") (pinfunction "10_10") (pintype "bidirectional"))
      (node (ref "U1") (pin "P$AC11") (pinfunction "P0.16_P$AC11") (pintype "bidirectional"))
    )
    (net (code "14") (name "GDR") (class "Default")
      (node (ref "J1") (pin "2") (pinfunction "2_2") (pintype "bidirectional"))
      (node (ref "Q3") (pin "1") (pinfunction "G_1") (pintype "bidirectional"))
      (node (ref "R2_EP_DR") (pin "2") (pinfunction "2_2") (pintype "bidirectional"))
    )
    (net (code "15") (name "GND") (class "Default")
      (node (ref "C1") (pin "2") (pinfunction "2_2") (pintype "passive"))
      (node (ref "C1-EP-DR") (pin "2") (pinfunction "2_2") (pintype "passive"))
      (node (ref "C10") (pin "2") (pinfunction "2_2") (pintype "passive"))
      (node (ref "C11") (pin "2") (pinfunction "2_2") (pintype "passive"))
      (node (ref "C12") (pin "2") (pinfunction "2_2") (pintype "passive"))
      (node (ref "C13") (pin "2") (pinfunction "2_2") (pintype "passive"))
      (node (ref "C14") (pin "2") (pinfunction "2_2") (pintype "passive"))
      (node (ref "C15") (pin "2") (pinfunction "2_2") (pintype "passive"))
      (node (ref "C16") (pin "2") (pinfunction "2_2") (pintype "passive"))
      (node (ref "C17") (pin "1") (pinfunction "1_1") (pintype "passive"))
      (node (ref "C18") (pin "1") (pinfunction "1_1") (pintype "passive"))
      (node (ref "C19") (pin "2") (pinfunction "2_2") (pintype "passive"))
      (node (ref "C2") (pin "2") (pinfunction "2_2") (pintype "passive"))
      (node (ref "C20") (pin "2") (pinfunction "2_2") (pintype "passive"))
      (node (ref "C21") (pin "2") (pinfunction "2_2") (pintype "passive"))
      (node (ref "C22") (pin "2") (pinfunction "2_2") (pintype "passive"))
      (node (ref "C23") (pin "1") (pinfunction "1_1") (pintype "passive"))
      (node (ref "C24") (pin "1") (pinfunction "1_1") (pintype "passive"))
      (node (ref "C25") (pin "2") (pinfunction "2_2") (pintype "passive"))
      (node (ref "C27") (pin "2") (pinfunction "2_2") (pintype "passive"))
      (node (ref "C29") (pin "2") (pinfunction "2_2") (pintype "passive"))
      (node (ref "C3") (pin "2") (pinfunction "2_2") (pintype "passive"))
      (node (ref "C30") (pin "2") (pinfunction "2_2") (pintype "passive"))
      (node (ref "C31") (pin "2") (pinfunction "2_2") (pintype "passive"))
      (node (ref "C32") (pin "2") (pinfunction "2_2") (pintype "passive"))
      (node (ref "C33") (pin "2") (pinfunction "2_2") (pintype "passive"))
      (node (ref "C34") (pin "2") (pinfunction "2_2") (pintype "passive"))
      (node (ref "C37") (pin "2") (pinfunction "2_2") (pintype "passive"))
      (node (ref "C38") (pin "2") (pinfunction "2_2") (pintype "passive"))
      (node (ref "C39") (pin "2") (pinfunction "2_2") (pintype "passive"))
      (node (ref "C4") (pin "2") (pinfunction "2_2") (pintype "passive"))
      (node (ref "C42") (pin "2") (pinfunction "2_2") (pintype "passive"))
      (node (ref "C43") (pin "2") (pinfunction "2_2") (pintype "passive"))
      (node (ref "C5") (pin "2") (pinfunction "2_2") (pintype "passive"))
      (node (ref "C6") (pin "2") (pinfunction "2_2") (pintype "passive"))
      (node (ref "C7") (pin "2") (pinfunction "2_2") (pintype "passive"))
      (node (ref "C8") (pin "2") (pinfunction "2_2") (pintype "passive"))
      (node (ref "C9") (pin "2") (pinfunction "2_2") (pintype "passive"))
      (node (ref "D3") (pin "2") (pinfunction "GND_2") (pintype "bidirectional"))
      (node (ref "D4") (pin "1") (pinfunction "K_1") (pintype "bidirectional"))
      (node (ref "EPD_C1") (pin "1") (pinfunction "1_1") (pintype "passive"))
      (node (ref "EPD_C10") (pin "1") (pinfunction "1_1") (pintype "passive"))
      (node (ref "EPD_C11") (pin "1") (pinfunction "1_1") (pintype "passive"))
      (node (ref "EPD_C12") (pin "1") (pinfunction "1_1") (pintype "passive"))
      (node (ref "EPD_C2") (pin "1") (pinfunction "1_1") (pintype "passive"))
      (node (ref "EPD_C5") (pin "1") (pinfunction "1_1") (pintype "passive"))
      (node (ref "EPD_C6") (pin "1") (pinfunction "1_1") (pintype "passive"))
      (node (ref "EPD_C7") (pin "1") (pinfunction "1_1") (pintype "passive"))
      (node (ref "EPD_C8") (pin "1") (pinfunction "1_1") (pintype "passive"))
      (node (ref "EPD_C9") (pin "1") (pinfunction "1_1") (pintype "passive"))
      (node (ref "IC1") (pin "D2") (pinfunction "GND_D2") (pintype "bidirectional"))
      (node (ref "IC2") (pin "B1") (pinfunction "IN/TRIG_B1") (pintype "bidirectional"))
      (node (ref "IC2") (pin "B3") (pinfunction "GND_B3") (pintype "bidirectional"))
      (node (ref "IC3") (pin "8") (pinfunction "GNDIO_8") (pintype "bidirectional"))
      (node (ref "IC3") (pin "9") (pinfunction "GND_9") (pintype "bidirectional"))
      (node (ref "IC9") (pin "B1") (pinfunction "VSEL_B1") (pintype "bidirectional"))
      (node (ref "IC9") (pin "C1") (pinfunction "AGND_C1") (pintype "bidirectional"))
      (node (ref "IC9") (pin "C2") (pinfunction "PGND_1_C2") (pintype "bidirectional"))
      (node (ref "IC9") (pin "C3") (pinfunction "PGND_2_C3") (pintype "bidirectional"))
      (node (ref "J1") (pin "17") (pinfunction "17_17") (pintype "bidirectional"))
      (node (ref "J1") (pin "8") (pinfunction "8_8") (pintype "bidirectional"))
      (node (ref "J1") (pin "MP1") (pinfunction "MP1_MP1") (pintype "bidirectional"))
      (node (ref "J1") (pin "MP2") (pinfunction "MP2_MP2") (pintype "bidirectional"))
      (node (ref "J2") (pin "3") (pinfunction "3_3") (pintype "bidirectional"))
      (node (ref "J2") (pin "5") (pinfunction "5_5") (pintype "bidirectional"))
      (node (ref "J4") (pin "A12_B1") (pinfunction "GND_A12_B1") (pintype "power_in"))
      (node (ref "J4") (pin "A1_B12") (pinfunction "GND_A1_B12") (pintype "power_in"))
      (node (ref "J4") (pin "SH1") (pinfunction "SHIELD_SH1") (pintype "passive"))
      (node (ref "J4") (pin "SH2") (pinfunction "SHIELD_SH2") (pintype "passive"))
      (node (ref "J4") (pin "SH3") (pinfunction "SHIELD_SH3") (pintype "passive"))
      (node (ref "J4") (pin "SH4") (pinfunction "SHIELD_SH4") (pintype "passive"))
      (node (ref "R1_USB") (pin "1") (pinfunction "1_1") (pintype "bidirectional"))
      (node (ref "R2_EP_DR") (pin "1") (pinfunction "1_1") (pintype "bidirectional"))
      (node (ref "R2_USB") (pin "2") (pinfunction "2_2") (pintype "bidirectional"))
      (node (ref "R3") (pin "1") (pinfunction "1_1") (pintype "bidirectional"))
      (node (ref "R9") (pin "1") (pinfunction "1_1") (pintype "bidirectional"))
      (node (ref "R_TYPE_SEL") (pin "1") (pinfunction "1_1") (pintype "bidirectional"))
      (node (ref "SJ1") (pin "1") (pinfunction "1_1") (pintype "passive"))
      (node (ref "SW_DN") (pin "1") (pinfunction "1_1") (pintype "passive"))
      (node (ref "SW_ENT") (pin "1") (pinfunction "1_1") (pintype "passive"))
      (node (ref "SW_UP") (pin "1") (pinfunction "1_1") (pintype "passive"))
      (node (ref "TP_BAT_GND") (pin "TP") (pinfunction "TP_TP") (pintype "input"))
      (node (ref "TP_GND") (pin "TP") (pinfunction "TP_TP") (pintype "input"))
      (node (ref "U1") (pin "P$74") (pinfunction "VSS_PAD_P$74") (pintype "bidirectional"))
      (node (ref "U1") (pin "P$75") (pinfunction "VSS_PAD_P$75") (pintype "bidirectional"))
      (node (ref "U1") (pin "P$76") (pinfunction "VSS_PAD_P$76") (pintype "bidirectional"))
      (node (ref "U1") (pin "P$77") (pinfunction "VSS_PAD_P$77") (pintype "bidirectional"))
      (node (ref "U1") (pin "P$78") (pinfunction "VSS_PAD_P$78") (pintype "bidirectional"))
      (node (ref "U1") (pin "P$79") (pinfunction "VSS_PAD_P$79") (pintype "bidirectional"))
      (node (ref "U1") (pin "P$80") (pinfunction "VSS_PAD_P$80") (pintype "bidirectional"))
      (node (ref "U1") (pin "P$81") (pinfunction "VSS_PAD_P$81") (pintype "bidirectional"))
      (node (ref "U1") (pin "P$82") (pinfunction "VSS_PAD_P$82") (pintype "bidirectional"))
      (node (ref "U1") (pin "P$83") (pinfunction "VSS_PAD_P$83") (pintype "bidirectional"))
      (node (ref "U1") (pin "P$84") (pinfunction "VSS_PAD_P$84") (pintype "bidirectional"))
      (node (ref "U1") (pin "P$85") (pinfunction "VSS_PAD_P$85") (pintype "bidirectional"))
      (node (ref "U1") (pin "P$86") (pinfunction "VSS_PAD_P$86") (pintype "bidirectional"))
      (node (ref "U1") (pin "P$87") (pinfunction "VSS_PAD_P$87") (pintype "bidirectional"))
      (node (ref "U1") (pin "P$88") (pinfunction "VSS_PAD_P$88") (pintype "bidirectional"))
      (node (ref "U1") (pin "P$89") (pinfunction "VSS_PAD_P$89") (pintype "bidirectional"))
      (node (ref "U1") (pin "P$90") (pinfunction "VSS_PAD_P$90") (pintype "bidirectional"))
      (node (ref "U1") (pin "P$B7") (pinfunction "VSS_P$B7") (pintype "power_in"))
      (node (ref "U1") (pin "P$F23") (pinfunction "VSS_PA_P$F23") (pintype "bidirectional"))
      (node (ref "U3") (pin "1") (pinfunction "CTG_1") (pintype "power_in"))
      (node (ref "U3") (pin "4") (pinfunction "GND_4") (pintype "power_in"))
      (node (ref "U3") (pin "6") (pinfunction "QSTRT_6") (pintype "input"))
      (node (ref "U3") (pin "9") (pinfunction "EP_9") (pintype "power_in"))
      (node (ref "X1") (pin "2") (pinfunction "2_2") (pintype "passive"))
      (node (ref "X1") (pin "4") (pinfunction "4_4") (pintype "passive"))
    )
    (net (code "16") (name "HAPTIC_EN") (class "Default")
      (node (ref "IC2") (pin "A1") (pinfunction "EN_A1") (pintype "bidirectional"))
      (node (ref "U1") (pin "P$U1") (pinfunction "P0.12_P$U1") (pintype "bidirectional"))
    )
    (net (code "17") (name "IMU_INT1") (class "Default")
      (node (ref "IC3") (pin "5") (pinfunction "INT1_5") (pintype "bidirectional"))
      (node (ref "U1") (pin "P$N1") (pinfunction "P0.08_P$N1") (pintype "bidirectional"))
    )
    (net (code "18") (name "IMU_INT2") (class "Default")
      (node (ref "IC3") (pin "6") (pinfunction "INT2_6") (pintype "bidirectional"))
      (node (ref "U1") (pin "P$P2") (pinfunction "P1.08_P$P2") (pintype "bidirectional"))
    )
    (net (code "19") (name "LX1") (class "Default")
      (node (ref "IC9") (pin "B2") (pinfunction "SW1_1_B2") (pintype "bidirectional"))
      (node (ref "IC9") (pin "B3") (pinfunction "SW1_2_B3") (pintype "bidirectional"))
      (node (ref "L7") (pin "1") (pinfunction "1_1") (pintype "bidirectional"))
    )
    (net (code "20") (name "LX2") (class "Default")
      (node (ref "IC9") (pin "D2") (pinfunction "SW2_1_D2") (pintype "bidirectional"))
      (node (ref "IC9") (pin "D3") (pinfunction "SW2_2_D3") (pintype "bidirectional"))
      (node (ref "L7") (pin "2") (pinfunction "2_2") (pintype "bidirectional"))
    )
    (net (code "21") (name "MOSI") (class "Default")
      (node (ref "J1") (pin "14") (pinfunction "14_14") (pintype "bidirectional"))
      (node (ref "U1") (pin "P$B13") (pinfunction "P0.03/AIN1_P$B13") (pintype "bidirectional"))
    )
    (net (code "22") (name "Net-(D2-K)") (class "Default")
      (node (ref "C2-EP-DR") (pin "1") (pinfunction "1_1") (pintype "passive"))
      (node (ref "D2") (pin "1") (pinfunction "K_1") (pintype "bidirectional"))
      (node (ref "D4") (pin "2") (pinfunction "A_2") (pintype "bidirectional"))
    )
    (net (code "23") (name "Net-(D5-A)") (class "Default")
      (node (ref "C2-EP-DR") (pin "2") (pinfunction "2_2") (pintype "passive"))
      (node (ref "D5") (pin "2") (pinfunction "A_2") (pintype "bidirectional"))
      (node (ref "L5") (pin "1") (pinfunction "1_1") (pintype "passive"))
      (node (ref "Q3") (pin "3") (pinfunction "D_3") (pintype "bidirectional"))
    )
    (net (code "24") (name "Net-(EPD_C1-Pad2)") (class "Default")
      (node (ref "EPD_C1") (pin "2") (pinfunction "2_2") (pintype "passive"))
      (node (ref "J1") (pin "5") (pinfunction "5_5") (pintype "bidirectional"))
    )
    (net (code "25") (name "Net-(EPD_C2-Pad2)") (class "Default")
      (node (ref "EPD_C2") (pin "2") (pinfunction "2_2") (pintype "passive"))
      (node (ref "J1") (pin "4") (pinfunction "4_4") (pintype "bidirectional"))
    )
    (net (code "26") (name "Net-(EPD_C6-Pad2)") (class "Default")
      (node (ref "EPD_C6") (pin "2") (pinfunction "2_2") (pintype "passive"))
      (node (ref "J1") (pin "18") (pinfunction "18_18") (pintype "bidirectional"))
    )
    (net (code "27") (name "Net-(EPD_C7-Pad2)") (class "Default")
      (node (ref "EPD_C7") (pin "2") (pinfunction "2_2") (pintype "passive"))
      (node (ref "J1") (pin "19") (pinfunction "19_19") (pintype "bidirectional"))
    )
    (net (code "28") (name "Net-(EPD_C8-Pad2)") (class "Default")
      (node (ref "EPD_C8") (pin "2") (pinfunction "2_2") (pintype "passive"))
      (node (ref "J1") (pin "20") (pinfunction "20_20") (pintype "bidirectional"))
    )
    (net (code "29") (name "Net-(EPD_C10-Pad2)") (class "Default")
      (node (ref "EPD_C10") (pin "2") (pinfunction "2_2") (pintype "passive"))
      (node (ref "J1") (pin "22") (pinfunction "22_22") (pintype "bidirectional"))
    )
    (net (code "30") (name "Net-(EPD_C12-Pad2)") (class "Default")
      (node (ref "EPD_C12") (pin "2") (pinfunction "2_2") (pintype "passive"))
      (node (ref "J1") (pin "24") (pinfunction "24_24") (pintype "bidirectional"))
    )
    (net (code "31") (name "Net-(IC1-TS{slash}MR)") (class "Default")
      (node (ref "IC1") (pin "D1") (pinfunction "TS/MR_D1") (pintype "bidirectional"))
      (node (ref "R9") (pin "2") (pinfunction "2_2") (pintype "bidirectional"))
    )
    (net (code "32") (name "Net-(IC2-REG)") (class "Default")
      (node (ref "C32") (pin "1") (pinfunction "1_1") (pintype "passive"))
      (node (ref "IC2") (pin "A2") (pinfunction "REG_A2") (pintype "bidirectional"))
    )
    (net (code "33") (name "Net-(IC3-SDO)") (class "Default")
      (node (ref "IC3") (pin "1") (pinfunction "SDO_1") (pintype "bidirectional"))
      (node (ref "R3") (pin "2") (pinfunction "2_2") (pintype "bidirectional"))
    )
    (net (code "34") (name "Net-(IC9-SCL)") (class "Default")
      (node (ref "IC9") (pin "D1") (pinfunction "SCL_D1") (pintype "bidirectional"))
      (node (ref "R4") (pin "2") (pinfunction "2_2") (pintype "bidirectional"))
    )
    (net (code "35") (name "Net-(IC9-SDA)") (class "Default")
      (node (ref "IC9") (pin "E1") (pinfunction "SDA_E1") (pintype "bidirectional"))
      (node (ref "R2") (pin "2") (pinfunction "2_2") (pintype "bidirectional"))
    )
    (net (code "36") (name "Net-(J4-CC1)") (class "Default")
      (node (ref "J4") (pin "A5") (pinfunction "CC1_A5") (pintype "bidirectional"))
      (node (ref "R1_USB") (pin "2") (pinfunction "2_2") (pintype "bidirectional"))
    )
    (net (code "37") (name "Net-(J4-CC2)") (class "Default")
      (node (ref "J4") (pin "B5") (pinfunction "CC2_B5") (pintype "bidirectional"))
      (node (ref "R2_USB") (pin "1") (pinfunction "1_1") (pintype "bidirectional"))
    )
    (net (code "38") (name "Net-(L2-Pad1)") (class "Default")
      (node (ref "L2") (pin "1") (pinfunction "1_1") (pintype "passive"))
      (node (ref "L3") (pin "2") (pinfunction "2_2") (pintype "passive"))
    )
    (net (code "39") (name "Net-(R1_EP_DR-Pad1)") (class "Default")
      (node (ref "R1_EP_DR") (pin "1") (pinfunction "1_1") (pintype "bidirectional"))
      (node (ref "R_TYPE_SEL") (pin "2") (pinfunction "2_2") (pintype "bidirectional"))
      (node (ref "SJ1") (pin "2") (pinfunction "2_2") (pintype "passive"))
    )
    (net (code "40") (name "Net-(U1-ANT)") (class "Default")
      (node (ref "C3") (pin "1") (pinfunction "1_1") (pintype "passive"))
      (node (ref "L1") (pin "1") (pinfunction "1_1") (pintype "passive"))
      (node (ref "U1") (pin "P$H23") (pinfunction "ANT_P$H23") (pintype "bidirectional"))
    )
    (net (code "41") (name "Net-(U1-DCC)") (class "Default")
      (node (ref "L2") (pin "2") (pinfunction "2_2") (pintype "passive"))
      (node (ref "U1") (pin "P$B3") (pinfunction "DCC_P$B3") (pintype "output"))
    )
    (net (code "42") (name "Net-(U1-DEC1)") (class "Default")
      (node (ref "C5") (pin "1") (pinfunction "1_1") (pintype "passive"))
      (node (ref "U1") (pin "P$C1") (pinfunction "DEC1_P$C1") (pintype "power_in"))
    )
    (net (code "43") (name "Net-(U1-DEC2)") (class "Default")
      (node (ref "C13") (pin "1") (pinfunction "1_1") (pintype "passive"))
      (node (ref "U1") (pin "P$A18") (pinfunction "DEC2_P$A18") (pintype "bidirectional"))
    )
    (net (code "44") (name "Net-(U1-DEC3V3)") (class "Default")
      (node (ref "C20") (pin "1") (pinfunction "1_1") (pintype "passive"))
      (node (ref "U1") (pin "P$AC5") (pinfunction "DEC3V3_P$AC5") (pintype "bidirectional"))
    )
    (net (code "45") (name "Net-(U1-DEC5)") (class "Default")
      (node (ref "C9") (pin "1") (pinfunction "1_1") (pintype "passive"))
      (node (ref "U1") (pin "P$N24") (pinfunction "DEC5_P$N24") (pintype "bidirectional"))
    )
    (net (code "46") (name "Net-(U1-P0.00{slash}XL1)") (class "Default")
      (node (ref "C17") (pin "2") (pinfunction "2_2") (pintype "passive"))
      (node (ref "U1") (pin "P$D2") (pinfunction "P0.00/XL1_P$D2") (pintype "bidirectional"))
      (node (ref "X2") (pin "2") (pinfunction "2_2") (pintype "passive"))
    )
    (net (code "47") (name "Net-(U1-P0.01{slash}XL2)") (class "Default")
      (node (ref "C18") (pin "2") (pinfunction "2_2") (pintype "passive"))
      (node (ref "U1") (pin "P$F2") (pinfunction "P0.01/XL2_P$F2") (pintype "bidirectional"))
      (node (ref "X2") (pin "1") (pinfunction "1_1") (pintype "passive"))
    )
    (net (code "48") (name "OUT+") (class "Default")
      (node (ref "IC2") (pin "A3") (pinfunction "OUT+_A3") (pintype "bidirectional"))
      (node (ref "TP_OP") (pin "TP") (pinfunction "TP_TP") (pintype "input"))
    )
    (net (code "49") (name "OUT-") (class "Default")
      (node (ref "IC2") (pin "C3") (pinfunction "OUT-_C3") (pintype "bidirectional"))
      (node (ref "TP_ON") (pin "TP") (pinfunction "TP_TP") (pintype "input"))
    )
    (net (code "50") (name "P0.09") (class "Default")
      (node (ref "U1") (pin "P$L24") (pinfunction "P0.09/NFC1_P$L24") (pintype "bidirectional"))
    )
    (net (code "51") (name "P0.13") (class "Default")
      (node (ref "C30") (pin "1") (pinfunction "1_1") (pintype "passive"))
      (node (ref "R5") (pin "1") (pinfunction "1_1") (pintype "bidirectional"))
      (node (ref "SW_UP") (pin "2") (pinfunction "2_2") (pintype "passive"))
      (node (ref "U1") (pin "P$AD8") (pinfunction "P0.13_P$AD8") (pintype "bidirectional"))
    )
    (net (code "52") (name "P0.14") (class "Default")
      (node (ref "C31") (pin "1") (pinfunction "1_1") (pintype "passive"))
      (node (ref "R8") (pin "1") (pinfunction "1_1") (pintype "bidirectional"))
      (node (ref "SW_ENT") (pin "2") (pinfunction "2_2") (pintype "passive"))
      (node (ref "U1") (pin "P$AC9") (pinfunction "P0.14_P$AC9") (pintype "bidirectional"))
    )
    (net (code "53") (name "P0.20") (class "Default")
      (node (ref "U1") (pin "P$AD16") (pinfunction "P0.20_P$AD16") (pintype "bidirectional"))
    )
    (net (code "54") (name "P0.21") (class "Default")
      (node (ref "U1") (pin "P$AC17") (pinfunction "P0.21_P$AC17") (pintype "bidirectional"))
    )
    (net (code "55") (name "P0.22") (class "Default")
      (node (ref "U1") (pin "P$AD18") (pinfunction "P0.22_P$AD18") (pintype "bidirectional"))
    )
    (net (code "56") (name "P0.23") (class "Default")
      (node (ref "U1") (pin "P$AC19") (pinfunction "P0.23_P$AC19") (pintype "bidirectional"))
    )
    (net (code "57") (name "P0.24") (class "Default")
      (node (ref "U1") (pin "P$AD20") (pinfunction "P0.24_P$AD20") (pintype "bidirectional"))
    )
    (net (code "58") (name "P0.25") (class "Default")
      (node (ref "U1") (pin "P$AC21") (pinfunction "P0.25_P$AC21") (pintype "bidirectional"))
    )
    (net (code "59") (name "P0.26") (class "Default")
      (node (ref "U1") (pin "P$G1") (pinfunction "P0.26_P$G1") (pintype "bidirectional"))
    )
    (net (code "60") (name "P0.27") (class "Default")
      (node (ref "U1") (pin "P$H2") (pinfunction "P0.27_P$H2") (pintype "bidirectional"))
    )
    (net (code "61") (name "P0.28") (class "Default")
      (node (ref "U1") (pin "P$B11") (pinfunction "P0.28/AIN4_P$B11") (pintype "bidirectional"))
    )
    (net (code "62") (name "P0.30") (class "Default")
      (node (ref "U1") (pin "P$B9") (pinfunction "P0.30/AIN6_P$B9") (pintype "bidirectional"))
    )
    (net (code "63") (name "P1.01") (class "Default")
      (node (ref "Q1") (pin "1") (pinfunction "G_1") (pintype "bidirectional"))
      (node (ref "R_PWR_EPD") (pin "1") (pinfunction "1_1") (pintype "bidirectional"))
      (node (ref "U1") (pin "P$Y23") (pinfunction "P1.01_P$Y23") (pintype "bidirectional"))
    )
    (net (code "64") (name "P1.02") (class "Default")
      (node (ref "C29") (pin "1") (pinfunction "1_1") (pintype "passive"))
      (node (ref "R7") (pin "1") (pinfunction "1_1") (pintype "bidirectional"))
      (node (ref "SW_DN") (pin "2") (pinfunction "2_2") (pintype "passive"))
      (node (ref "U1") (pin "P$W24") (pinfunction "P1.02_P$W24") (pintype "bidirectional"))
    )
    (net (code "65") (name "P1.03") (class "Default")
      (node (ref "U1") (pin "P$V23") (pinfunction "P1.03_P$V23") (pintype "bidirectional"))
    )
    (net (code "66") (name "P1.04") (class "Default")
      (node (ref "U1") (pin "P$U24") (pinfunction "P1.04_P$U24") (pintype "bidirectional"))
    )
    (net (code "67") (name "P1.05") (class "Default")
      (node (ref "U1") (pin "P$T23") (pinfunction "P1.05_P$T23") (pintype "bidirectional"))
    )
    (net (code "68") (name "P1.06") (class "Default")
      (node (ref "U1") (pin "P$R24") (pinfunction "P1.06_P$R24") (pintype "bidirectional"))
    )
    (net (code "69") (name "P1.07") (class "Default")
      (node (ref "U1") (pin "P$P23") (pinfunction "P1.07_P$P23") (pintype "bidirectional"))
    )
    (net (code "70") (name "P1.10") (class "Default")
      (node (ref "U1") (pin "P$A20") (pinfunction "P1.10_P$A20") (pintype "bidirectional"))
    )
    (net (code "71") (name "P1.11") (class "Default")
      (node (ref "U1") (pin "P$B19") (pinfunction "P1.11_P$B19") (pintype "bidirectional"))
    )
    (net (code "72") (name "P1.12") (class "Default")
      (node (ref "U1") (pin "P$B17") (pinfunction "P1.12_P$B17") (pintype "bidirectional"))
    )
    (net (code "73") (name "P1.13") (class "Default")
      (node (ref "U1") (pin "P$A16") (pinfunction "P1.13_P$A16") (pintype "bidirectional"))
    )
    (net (code "74") (name "P1.14") (class "Default")
      (node (ref "U1") (pin "P$B15") (pinfunction "P1.14_P$B15") (pintype "bidirectional"))
    )
    (net (code "75") (name "P1.15") (class "Default")
      (node (ref "U1") (pin "P$A14") (pinfunction "P1.15_P$A14") (pintype "bidirectional"))
    )
    (net (code "76") (name "PMIC_INT") (class "Default")
      (node (ref "IC1") (pin "A1") (pinfunction "~{INT}_A1") (pintype "bidirectional"))
      (node (ref "U1") (pin "P$T2") (pinfunction "P0.11_P$T2") (pintype "bidirectional"))
    )
    (net (code "77") (name "PREVGH") (class "Default")
      (node (ref "D5") (pin "1") (pinfunction "K_1") (pintype "bidirectional"))
      (node (ref "EPD_C9") (pin "2") (pinfunction "2_2") (pintype "passive"))
      (node (ref "J1") (pin "21") (pinfunction "21_21") (pintype "bidirectional"))
    )
    (net (code "78") (name "PREVGL") (class "Default")
      (node (ref "D2") (pin "2") (pinfunction "A_2") (pintype "bidirectional"))
      (node (ref "EPD_C11") (pin "2") (pinfunction "2_2") (pintype "passive"))
      (node (ref "J1") (pin "23") (pinfunction "23_23") (pintype "bidirectional"))
    )
    (net (code "79") (name "RESE") (class "Default")
      (node (ref "J1") (pin "3") (pinfunction "3_3") (pintype "bidirectional"))
      (node (ref "Q3") (pin "2") (pinfunction "S_2") (pintype "bidirectional"))
      (node (ref "R1_EP_DR") (pin "2") (pinfunction "2_2") (pintype "bidirectional"))
    )
    (net (code "80") (name "RESET") (class "Default")
      (node (ref "J2") (pin "6") (pinfunction "6_6") (pintype "bidirectional"))
      (node (ref "TP_RESET") (pin "TP") (pinfunction "TP_TP") (pintype "input"))
      (node (ref "U1") (pin "P$AC13") (pinfunction "P0.18/RESET_P$AC13") (pintype "bidirectional"))
      (node (ref "U1") (pin "P$AC15") (pinfunction "P0.19_P$AC15") (pintype "bidirectional"))
    )
    (net (code "81") (name "RF") (class "Default")
      (node (ref "ANT1") (pin "1") (pinfunction "FEED_1") (pintype "input"))
      (node (ref "C22") (pin "1") (pinfunction "1_1") (pintype "passive"))
      (node (ref "C4") (pin "1") (pinfunction "1_1") (pintype "passive"))
      (node (ref "L1") (pin "2") (pinfunction "2_2") (pintype "passive"))
    )
    (net (code "82") (name "SCK") (class "Default")
      (node (ref "J1") (pin "13") (pinfunction "13_13") (pintype "bidirectional"))
      (node (ref "U1") (pin "P$A12") (pinfunction "P0.02/AIN0_P$A12") (pintype "bidirectional"))
    )
    (net (code "83") (name "SCL") (class "Default")
      (node (ref "IC1") (pin "B1") (pinfunction "SCL_B1") (pintype "bidirectional"))
      (node (ref "IC2") (pin "C1") (pinfunction "SCL_C1") (pintype "bidirectional"))
      (node (ref "IC3") (pin "12") (pinfunction "SCX_12") (pintype "bidirectional"))
      (node (ref "R17") (pin "2") (pinfunction "2_2") (pintype "bidirectional"))
      (node (ref "R4") (pin "1") (pinfunction "1_1") (pintype "bidirectional"))
      (node (ref "TP_SCL") (pin "TP") (pinfunction "TP_TP") (pintype "input"))
      (node (ref "U1") (pin "P$M2") (pinfunction "P0.07_P$M2") (pintype "bidirectional"))
      (node (ref "U3") (pin "7") (pinfunction "SCL_7") (pintype "input"))
    )
    (net (code "84") (name "SDA") (class "Default")
      (node (ref "IC1") (pin "C1") (pinfunction "SDA_C1") (pintype "bidirectional"))
      (node (ref "IC2") (pin "B2") (pinfunction "SDA_B2") (pintype "bidirectional"))
      (node (ref "IC3") (pin "2") (pinfunction "SDX_2") (pintype "bidirectional"))
      (node (ref "R18") (pin "2") (pinfunction "2_2") (pintype "bidirectional"))
      (node (ref "R2") (pin "1") (pinfunction "1_1") (pintype "bidirectional"))
      (node (ref "TP_SDA") (pin "TP") (pinfunction "TP_TP") (pintype "input"))
      (node (ref "U1") (pin "P$L1") (pinfunction "P0.06_P$L1") (pintype "bidirectional"))
      (node (ref "U3") (pin "8") (pinfunction "SDA_8") (pintype "bidirectional"))
    )
    (net (code "85") (name "SWDCLK") (class "Default")
      (node (ref "J2") (pin "4") (pinfunction "4_4") (pintype "bidirectional"))
      (node (ref "TP_SWDCLK") (pin "TP") (pinfunction "TP_TP") (pintype "input"))
      (node (ref "U1") (pin "P$AA24") (pinfunction "SWDCLK_P$AA24") (pintype "input"))
    )
    (net (code "86") (name "SWDIO") (class "Default")
      (node (ref "J2") (pin "2") (pinfunction "2_2") (pintype "bidirectional"))
      (node (ref "TP_SWDIO") (pin "TP") (pinfunction "TP_TP") (pintype "input"))
      (node (ref "U1") (pin "P$AC24") (pinfunction "SWDIO_P$AC24") (pintype "bidirectional"))
    )
    (net (code "87") (name "SWO") (class "Default")
      (node (ref "TP_SWO") (pin "TP") (pinfunction "TP_TP") (pintype "input"))
      (node (ref "U1") (pin "P$AD22") (pinfunction "P1.00_P$AD22") (pintype "bidirectional"))
    )
    (net (code "88") (name "VBAT") (class "Default")
      (node (ref "C27") (pin "1") (pinfunction "1_1") (pintype "passive"))
      (node (ref "C37") (pin "1") (pinfunction "1_1") (pintype "passive"))
      (node (ref "IC1") (pin "C2") (pinfunction "BAT_C2") (pintype "bidirectional"))
      (node (ref "TP_VBAT") (pin "TP") (pinfunction "TP_TP") (pintype "input"))
      (node (ref "U3") (pin "2") (pinfunction "CELL_2") (pintype "power_in"))
      (node (ref "U3") (pin "3") (pinfunction "VDD_3") (pintype "power_in"))
    )
    (net (code "89") (name "VBUS") (class "Default")
      (node (ref "C21") (pin "1") (pinfunction "1_1") (pintype "passive"))
      (node (ref "C38") (pin "1") (pinfunction "1_1") (pintype "passive"))
      (node (ref "C42") (pin "1") (pinfunction "1_1") (pintype "passive"))
      (node (ref "C43") (pin "1") (pinfunction "1_1") (pintype "passive"))
      (node (ref "D3") (pin "5") (pinfunction "VBUS_5") (pintype "bidirectional"))
      (node (ref "IC1") (pin "A2") (pinfunction "IN_A2") (pintype "bidirectional"))
      (node (ref "J4") (pin "A4_B9") (pinfunction "VBUS_A4_B9") (pintype "power_in"))
      (node (ref "J4") (pin "A9_B4") (pinfunction "VBUS_A9_B4") (pintype "power_in"))
      (node (ref "U1") (pin "P$AD2") (pinfunction "VBUS_P$AD2") (pintype "power_in"))
    )
    (net (code "90") (name "VREG") (class "Default")
      (node (ref "C23") (pin "2") (pinfunction "2_2") (pintype "passive"))
      (node (ref "C24") (pin "2") (pinfunction "2_2") (pintype "passive"))
      (node (ref "C39") (pin "1") (pinfunction "1_1") (pintype "passive"))
      (node (ref "IC1") (pin "B2") (pinfunction "SYS_B2") (pintype "bidirectional"))
      (node (ref "IC9") (pin "A1") (pinfunction "EN_A1") (pintype "bidirectional"))
      (node (ref "IC9") (pin "A2") (pinfunction "VIN_1_A2") (pintype "bidirectional"))
      (node (ref "IC9") (pin "A3") (pinfunction "VIN_2_A3") (pintype "bidirectional"))
      (node (ref "TP_VREG") (pin "TP") (pinfunction "TP_TP") (pintype "input"))
    )
    (net (code "91") (name "XC1") (class "Default")
      (node (ref "C1") (pin "1") (pinfunction "1_1") (pintype "passive"))
      (node (ref "U1") (pin "P$B24") (pinfunction "XC1_P$B24") (pintype "input"))
      (node (ref "X1") (pin "1") (pinfunction "1_1") (pintype "passive"))
    )
    (net (code "92") (name "XC2") (class "Default")
      (node (ref "C2") (pin "1") (pinfunction "1_1") (pintype "passive"))
      (node (ref "U1") (pin "P$A23") (pinfunction "XC2_P$A23") (pintype "output"))
      (node (ref "X1") (pin "3") (pinfunction "3_3") (pintype "passive"))
    )
    (net (code "93") (name "unconnected-(ANT1-NC-Pad2)") (class "Default")
      (node (ref "ANT1") (pin "2") (pinfunction "NC_2") (pintype "no_connect"))
    )
    (net (code "94") (name "unconnected-(IC3-ASCL-Pad11)") (class "Default")
      (node (ref "IC3") (pin "11") (pinfunction "ASCL_11") (pintype "bidirectional"))
    )
    (net (code "95") (name "unconnected-(IC3-ASDA-Pad4)") (class "Default")
      (node (ref "IC3") (pin "4") (pinfunction "ASDA_4") (pintype "bidirectional"))
    )
    (net (code "96") (name "unconnected-(J1-Pad1)") (class "Default")
      (node (ref "J1") (pin "1") (pinfunction "1_1") (pintype "bidirectional"))
    )
    (net (code "97") (name "unconnected-(J1-Pad6)") (class "Default")
      (node (ref "J1") (pin "6") (pinfunction "6_6") (pintype "bidirectional"))
    )
    (net (code "98") (name "unconnected-(J1-Pad7)") (class "Default")
      (node (ref "J1") (pin "7") (pinfunction "7_7") (pintype "bidirectional"))
    )
    (net (code "99") (name "unconnected-(J4-SBU1-PadA8)") (class "Default")
      (node (ref "J4") (pin "A8") (pinfunction "SBU1_A8") (pintype "bidirectional"))
    )
    (net (code "100") (name "unconnected-(J4-SBU2-PadB8)") (class "Default")
      (node (ref "J4") (pin "B8") (pinfunction "SBU2_B8") (pintype "bidirectional"))
    )
    (net (code "101") (name "unconnected-(U1-DCCH-PadP$AB2)") (class "Default")
      (node (ref "U1") (pin "P$AB2") (pinfunction "DCCH_P$AB2") (pintype "bidirectional"))
    )
  )
)
